# furby_connector.net
KiCad netlist of a schematic drawn in EAGLE
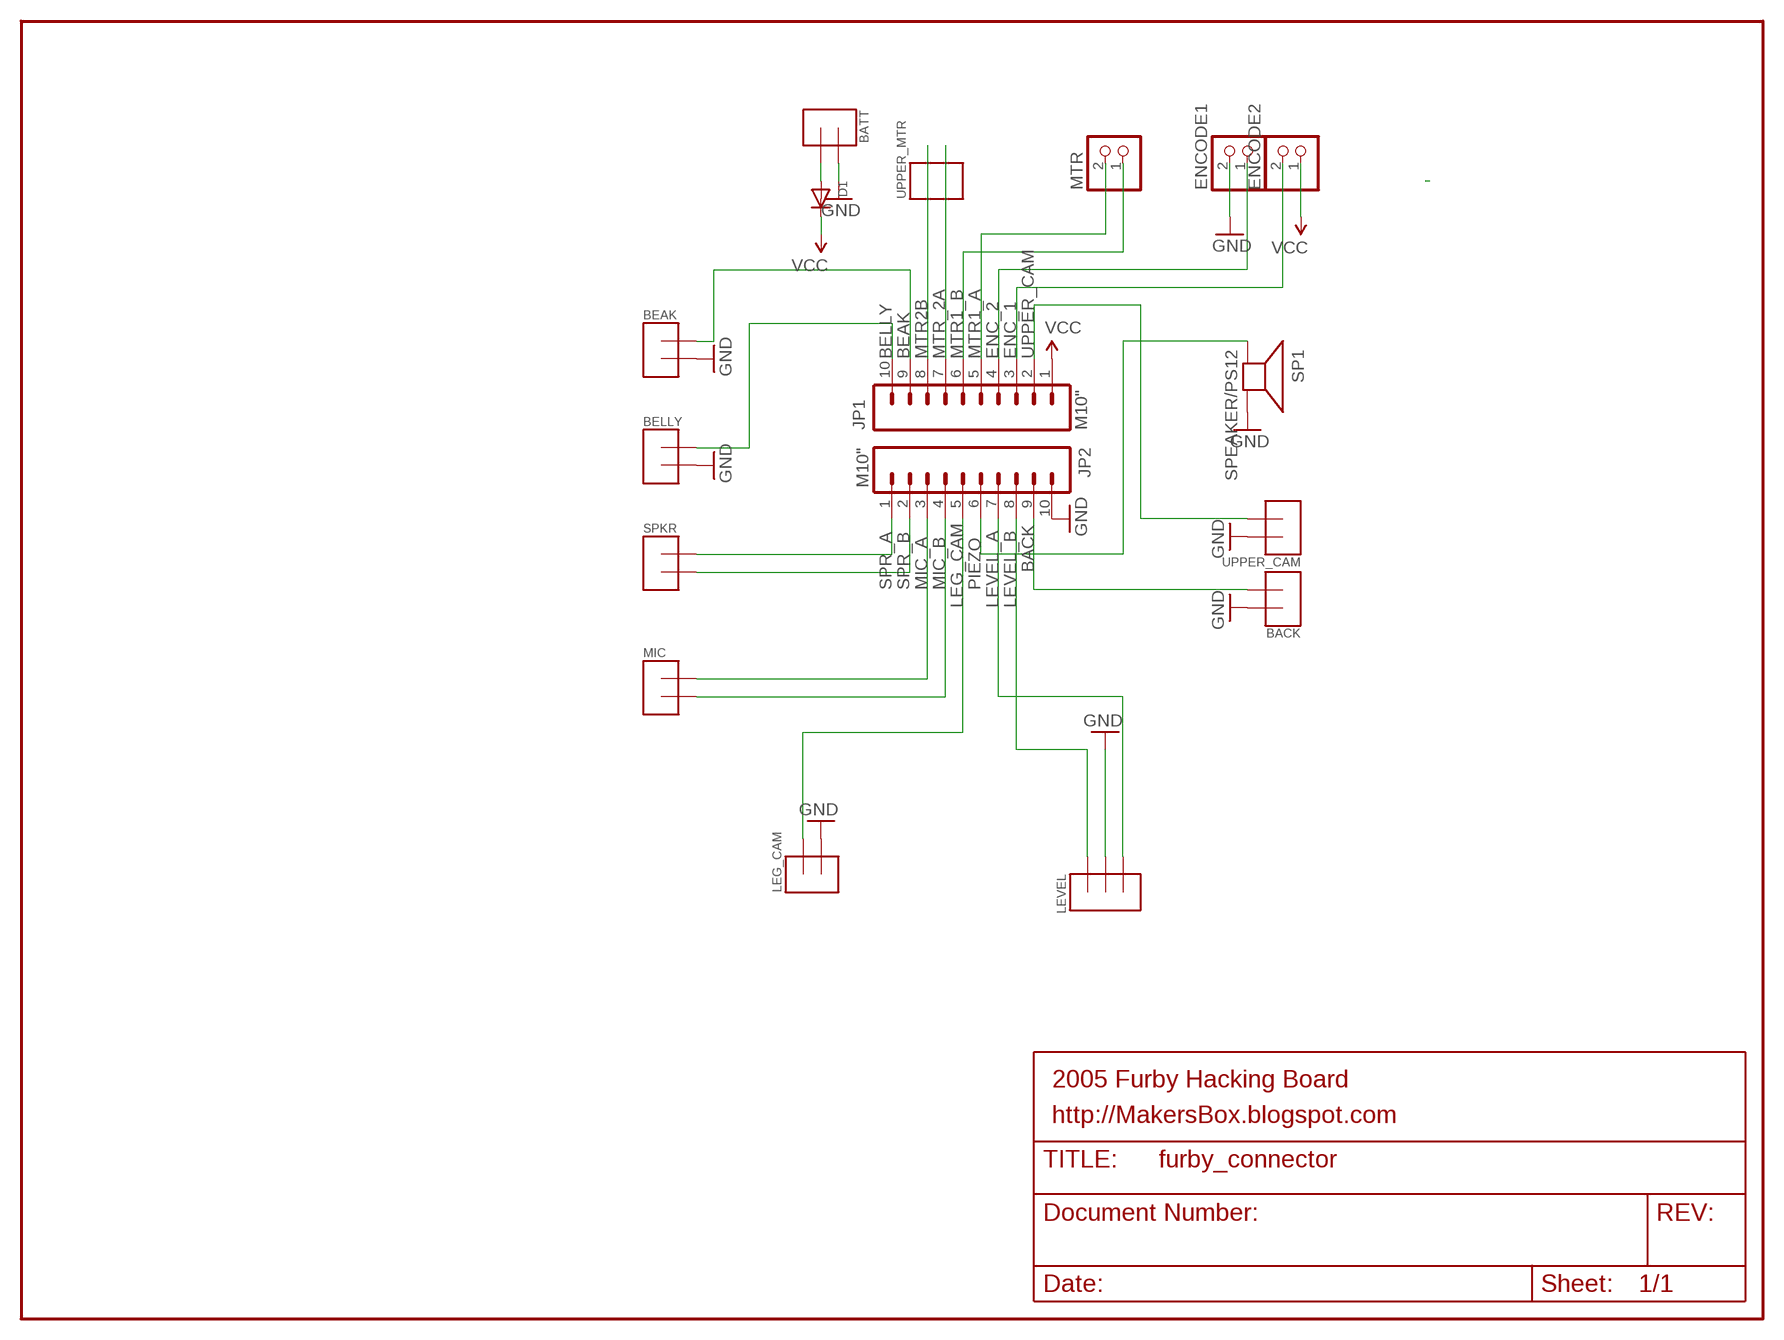
[diagram p0: schematic, sheet 1]

(export (version "E")
  (design (tool "Eeschema 10.0.6"))
  (components
    (comp (ref "BACK")
      (value "TERMINAL2")
      (footprint "eagle-import:TERMINAL_2")
      (libsource (lib "eagle-import") (part "TERMINAL2"))
    )
    (comp (ref "BATT")
      (value "TERMINAL2")
      (footprint "eagle-import:TERMINAL_2")
      (libsource (lib "eagle-import") (part "TERMINAL2"))
    )
    (comp (ref "BEAK")
      (value "TERMINAL2")
      (footprint "eagle-import:TERMINAL_2")
      (libsource (lib "eagle-import") (part "TERMINAL2"))
    )
    (comp (ref "BELLY")
      (value "TERMINAL2")
      (footprint "eagle-import:TERMINAL_2")
      (libsource (lib "eagle-import") (part "TERMINAL2"))
    )
    (comp (ref "D1")
      (value "DIODEDO-1N4148")
      (footprint "eagle-import:DO-1N4148")
      (libsource (lib "eagle-import") (part "DIODEDO-1N4148"))
    )
    (comp (ref "ENCODE1")
      (value "JST_2PIN-THM")
      (footprint "eagle-import:JST-PH-2-THM")
      (libsource (lib "eagle-import") (part "JST_2PIN-THM"))
    )
    (comp (ref "ENCODE2")
      (value "JST_2PIN-THM")
      (footprint "eagle-import:JST-PH-2-THM")
      (libsource (lib "eagle-import") (part "JST_2PIN-THM"))
    )
    (comp (ref "JP1")
      (value "M10\"")
      (footprint "eagle-import:1X10")
      (libsource (lib "eagle-import") (part "M10{dblquote}"))
    )
    (comp (ref "JP2")
      (value "M10\"")
      (footprint "eagle-import:1X10")
      (libsource (lib "eagle-import") (part "M10{dblquote}"))
    )
    (comp (ref "LEG_CAM")
      (value "TERMINAL2")
      (footprint "eagle-import:TERMINAL_2")
      (libsource (lib "eagle-import") (part "TERMINAL2"))
    )
    (comp (ref "LEVEL")
      (value "TERMINAL")
      (footprint "eagle-import:TERMINAL_3")
      (libsource (lib "eagle-import") (part "TERMINAL"))
    )
    (comp (ref "MIC")
      (value "TERMINAL2")
      (footprint "eagle-import:TERMINAL_2")
      (libsource (lib "eagle-import") (part "TERMINAL2"))
    )
    (comp (ref "MTR")
      (value "JST_2PIN-THM")
      (footprint "eagle-import:JST-PH-2-THM")
      (libsource (lib "eagle-import") (part "JST_2PIN-THM"))
    )
    (comp (ref "SP1")
      (value "SPEAKER/PS12")
      (footprint "eagle-import:PS12")
      (libsource (lib "eagle-import") (part "SPEAKER/PS12"))
    )
    (comp (ref "SPKR")
      (value "TERMINAL2")
      (footprint "eagle-import:TERMINAL_2")
      (libsource (lib "eagle-import") (part "TERMINAL2"))
    )
    (comp (ref "UPPER_CAM")
      (value "TERMINAL2")
      (footprint "eagle-import:TERMINAL_2")
      (libsource (lib "eagle-import") (part "TERMINAL2"))
    )
    (comp (ref "UPPER_MTR")
      (value "TERMINAL2")
      (footprint "eagle-import:TERMINAL_2")
      (libsource (lib "eagle-import") (part "TERMINAL2"))
    )
  )
  (nets
    (net (code "1") (name "/BACK") (class "Default")
      (node (ref "BACK") (pin "P$2") (pinfunction "P$2_P$2") (pintype "bidirectional"))
      (node (ref "JP2") (pin "9") (pinfunction "9_9") (pintype "passive"))
    )
    (net (code "2") (name "/BEAK") (class "Default")
      (node (ref "BEAK") (pin "P$1") (pinfunction "P$1_P$1") (pintype "bidirectional"))
      (node (ref "JP1") (pin "9") (pinfunction "9_9") (pintype "passive"))
    )
    (net (code "3") (name "/BELLY") (class "Default")
      (node (ref "BELLY") (pin "P$1") (pinfunction "P$1_P$1") (pintype "bidirectional"))
      (node (ref "JP1") (pin "10") (pinfunction "10_10") (pintype "passive"))
    )
    (net (code "4") (name "/ENC_1") (class "Default")
      (node (ref "ENCODE2") (pin "2") (pinfunction "1_2") (pintype "passive"))
      (node (ref "JP1") (pin "3") (pinfunction "3_3") (pintype "passive"))
    )
    (net (code "5") (name "/ENC_2") (class "Default")
      (node (ref "ENCODE1") (pin "1") (pinfunction "2_1") (pintype "passive"))
      (node (ref "JP1") (pin "4") (pinfunction "4_4") (pintype "passive"))
    )
    (net (code "6") (name "/LEG_CAM") (class "Default")
      (node (ref "JP2") (pin "5") (pinfunction "5_5") (pintype "passive"))
      (node (ref "LEG_CAM") (pin "P$1") (pinfunction "P$1_P$1") (pintype "bidirectional"))
    )
    (net (code "7") (name "/LEVEL_A") (class "Default")
      (node (ref "JP2") (pin "7") (pinfunction "7_7") (pintype "passive"))
      (node (ref "LEVEL") (pin "P$3") (pinfunction "P$3_P$3") (pintype "bidirectional"))
    )
    (net (code "8") (name "/LEVEL_B") (class "Default")
      (node (ref "JP2") (pin "8") (pinfunction "8_8") (pintype "passive"))
      (node (ref "LEVEL") (pin "P$1") (pinfunction "P$1_P$1") (pintype "bidirectional"))
    )
    (net (code "9") (name "/MIC_A") (class "Default")
      (node (ref "JP2") (pin "3") (pinfunction "3_3") (pintype "passive"))
      (node (ref "MIC") (pin "P$1") (pinfunction "P$1_P$1") (pintype "bidirectional"))
    )
    (net (code "10") (name "/MIC_B") (class "Default")
      (node (ref "JP2") (pin "4") (pinfunction "4_4") (pintype "passive"))
      (node (ref "MIC") (pin "P$2") (pinfunction "P$2_P$2") (pintype "bidirectional"))
    )
    (net (code "11") (name "/MTR1_A") (class "Default")
      (node (ref "JP1") (pin "5") (pinfunction "5_5") (pintype "passive"))
      (node (ref "MTR") (pin "2") (pinfunction "1_2") (pintype "passive"))
    )
    (net (code "12") (name "/MTR1_B") (class "Default")
      (node (ref "JP1") (pin "6") (pinfunction "6_6") (pintype "passive"))
      (node (ref "MTR") (pin "1") (pinfunction "2_1") (pintype "passive"))
    )
    (net (code "13") (name "/MTR2B") (class "Default")
      (node (ref "JP1") (pin "8") (pinfunction "8_8") (pintype "passive"))
      (node (ref "UPPER_MTR") (pin "P$1") (pinfunction "P$1_P$1") (pintype "bidirectional"))
    )
    (net (code "14") (name "/MTR_2A") (class "Default")
      (node (ref "JP1") (pin "7") (pinfunction "7_7") (pintype "passive"))
      (node (ref "UPPER_MTR") (pin "P$2") (pinfunction "P$2_P$2") (pintype "bidirectional"))
    )
    (net (code "15") (name "/PIEZO") (class "Default")
      (node (ref "JP2") (pin "6") (pinfunction "6_6") (pintype "passive"))
      (node (ref "SP1") (pin "P$1") (pinfunction "+_P$1") (pintype "passive"))
    )
    (net (code "16") (name "/SPR_A") (class "Default")
      (node (ref "JP2") (pin "1") (pinfunction "1_1") (pintype "passive"))
      (node (ref "SPKR") (pin "P$1") (pinfunction "P$1_P$1") (pintype "bidirectional"))
    )
    (net (code "17") (name "/SPR_B") (class "Default")
      (node (ref "JP2") (pin "2") (pinfunction "2_2") (pintype "passive"))
      (node (ref "SPKR") (pin "P$2") (pinfunction "P$2_P$2") (pintype "bidirectional"))
    )
    (net (code "18") (name "/UPPER_CAM") (class "Default")
      (node (ref "JP1") (pin "2") (pinfunction "2_2") (pintype "passive"))
      (node (ref "UPPER_CAM") (pin "P$2") (pinfunction "P$2_P$2") (pintype "bidirectional"))
    )
    (net (code "19") (name "GND") (class "Default")
      (node (ref "BACK") (pin "P$1") (pinfunction "P$1_P$1") (pintype "bidirectional"))
      (node (ref "BATT") (pin "P$1") (pinfunction "P$1_P$1") (pintype "bidirectional"))
      (node (ref "BEAK") (pin "P$2") (pinfunction "P$2_P$2") (pintype "bidirectional"))
      (node (ref "BELLY") (pin "P$2") (pinfunction "P$2_P$2") (pintype "bidirectional"))
      (node (ref "ENCODE1") (pin "2") (pinfunction "1_2") (pintype "passive"))
      (node (ref "JP2") (pin "10") (pinfunction "10_10") (pintype "passive"))
      (node (ref "LEG_CAM") (pin "P$2") (pinfunction "P$2_P$2") (pintype "bidirectional"))
      (node (ref "LEVEL") (pin "P$2") (pinfunction "P$2_P$2") (pintype "bidirectional"))
      (node (ref "SP1") (pin "P$2") (pinfunction "-_P$2") (pintype "passive"))
      (node (ref "UPPER_CAM") (pin "P$1") (pinfunction "P$1_P$1") (pintype "bidirectional"))
    )
    (net (code "20") (name "Net-(BATT-PadP$2)") (class "Default")
      (node (ref "BATT") (pin "P$2") (pinfunction "P$2_P$2") (pintype "bidirectional"))
      (node (ref "D1") (pin "A") (pinfunction "A_A") (pintype "passive"))
    )
    (net (code "21") (name "VCC") (class "Default")
      (node (ref "D1") (pin "C") (pinfunction "C_C") (pintype "passive"))
      (node (ref "ENCODE2") (pin "1") (pinfunction "2_1") (pintype "passive"))
      (node (ref "JP1") (pin "1") (pinfunction "1_1") (pintype "passive"))
    )
  )
)
